# jumper_bed2.net
KiCad netlist of a schematic drawn in EAGLE
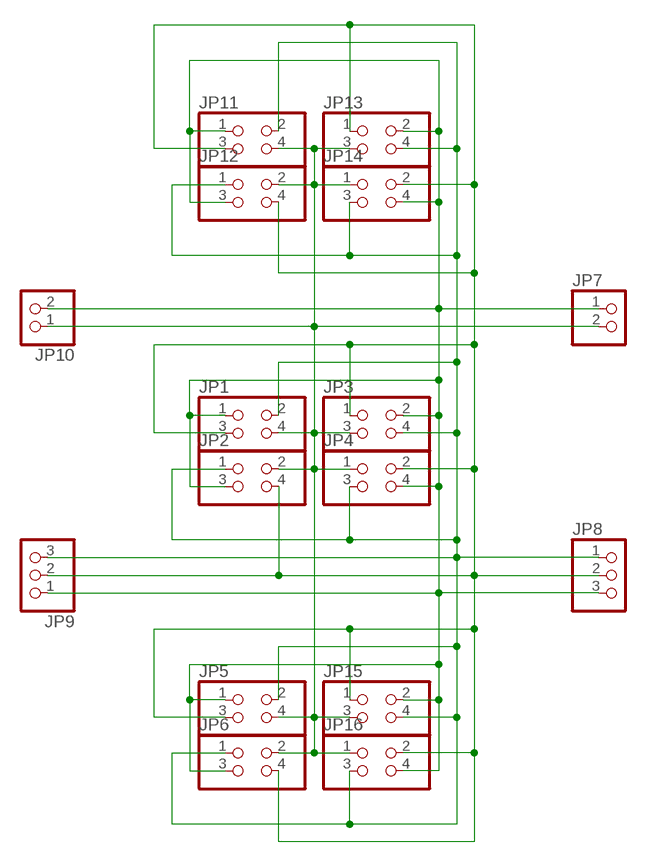
[diagram p0: schematic, sheet 1]

(export (version "E")
  (design (tool "Eeschema 10.0.6"))
  (components
    (comp (ref "JP1")
      (value "PINHD-2X2")
      (footprint "eagle-import:2X02")
      (libsource (lib "eagle-import") (part "PINHD-2X2"))
    )
    (comp (ref "JP2")
      (value "PINHD-2X2")
      (footprint "eagle-import:2X02")
      (libsource (lib "eagle-import") (part "PINHD-2X2"))
    )
    (comp (ref "JP3")
      (value "PINHD-2X2")
      (footprint "eagle-import:2X02")
      (libsource (lib "eagle-import") (part "PINHD-2X2"))
    )
    (comp (ref "JP4")
      (value "PINHD-2X2")
      (footprint "eagle-import:2X02")
      (libsource (lib "eagle-import") (part "PINHD-2X2"))
    )
    (comp (ref "JP5")
      (value "PINHD-2X2")
      (footprint "eagle-import:2X02")
      (libsource (lib "eagle-import") (part "PINHD-2X2"))
    )
    (comp (ref "JP6")
      (value "PINHD-2X2")
      (footprint "eagle-import:2X02")
      (libsource (lib "eagle-import") (part "PINHD-2X2"))
    )
    (comp (ref "JP7")
      (value "PINHD-1X2/90")
      (footprint "eagle-import:1X02_90")
      (libsource (lib "eagle-import") (part "PINHD-1X2/90"))
    )
    (comp (ref "JP8")
      (value "PINHD-1X3/90")
      (footprint "eagle-import:1X03_90")
      (libsource (lib "eagle-import") (part "PINHD-1X3/90"))
    )
    (comp (ref "JP9")
      (value "PINHD-1X31X03/90F")
      (footprint "eagle-import:1X03_90F")
      (libsource (lib "eagle-import") (part "PINHD-1X31X03/90F"))
    )
    (comp (ref "JP10")
      (value "PINHD-1X21X02/90F")
      (footprint "eagle-import:1X02_90F")
      (libsource (lib "eagle-import") (part "PINHD-1X21X02/90F"))
    )
    (comp (ref "JP11")
      (value "PINHD-2X2")
      (footprint "eagle-import:2X02")
      (libsource (lib "eagle-import") (part "PINHD-2X2"))
    )
    (comp (ref "JP12")
      (value "PINHD-2X2")
      (footprint "eagle-import:2X02")
      (libsource (lib "eagle-import") (part "PINHD-2X2"))
    )
    (comp (ref "JP13")
      (value "PINHD-2X2")
      (footprint "eagle-import:2X02")
      (libsource (lib "eagle-import") (part "PINHD-2X2"))
    )
    (comp (ref "JP14")
      (value "PINHD-2X2")
      (footprint "eagle-import:2X02")
      (libsource (lib "eagle-import") (part "PINHD-2X2"))
    )
    (comp (ref "JP15")
      (value "PINHD-2X2")
      (footprint "eagle-import:2X02")
      (libsource (lib "eagle-import") (part "PINHD-2X2"))
    )
    (comp (ref "JP16")
      (value "PINHD-2X2")
      (footprint "eagle-import:2X02")
      (libsource (lib "eagle-import") (part "PINHD-2X2"))
    )
  )
  (nets
    (net (code "1") (name "Net-(JP1-Pad1)") (class "Default")
      (node (ref "JP1") (pin "1") (pinfunction "1_1") (pintype "passive"))
      (node (ref "JP10") (pin "2") (pinfunction "2_2") (pintype "passive"))
      (node (ref "JP11") (pin "1") (pinfunction "1_1") (pintype "passive"))
      (node (ref "JP12") (pin "3") (pinfunction "3_3") (pintype "passive"))
      (node (ref "JP13") (pin "2") (pinfunction "2_2") (pintype "passive"))
      (node (ref "JP14") (pin "4") (pinfunction "4_4") (pintype "passive"))
      (node (ref "JP15") (pin "2") (pinfunction "2_2") (pintype "passive"))
      (node (ref "JP16") (pin "4") (pinfunction "4_4") (pintype "passive"))
      (node (ref "JP2") (pin "3") (pinfunction "3_3") (pintype "passive"))
      (node (ref "JP3") (pin "2") (pinfunction "2_2") (pintype "passive"))
      (node (ref "JP4") (pin "4") (pinfunction "4_4") (pintype "passive"))
      (node (ref "JP5") (pin "1") (pinfunction "1_1") (pintype "passive"))
      (node (ref "JP6") (pin "3") (pinfunction "3_3") (pintype "passive"))
      (node (ref "JP7") (pin "1") (pinfunction "1_1") (pintype "passive"))
      (node (ref "JP8") (pin "3") (pinfunction "3_3") (pintype "passive"))
      (node (ref "JP9") (pin "1") (pinfunction "1_1") (pintype "passive"))
    )
    (net (code "2") (name "Net-(JP1-Pad2)") (class "Default")
      (node (ref "JP1") (pin "2") (pinfunction "2_2") (pintype "passive"))
      (node (ref "JP11") (pin "2") (pinfunction "2_2") (pintype "passive"))
      (node (ref "JP12") (pin "1") (pinfunction "1_1") (pintype "passive"))
      (node (ref "JP13") (pin "4") (pinfunction "4_4") (pintype "passive"))
      (node (ref "JP14") (pin "3") (pinfunction "3_3") (pintype "passive"))
      (node (ref "JP15") (pin "4") (pinfunction "4_4") (pintype "passive"))
      (node (ref "JP16") (pin "3") (pinfunction "3_3") (pintype "passive"))
      (node (ref "JP2") (pin "1") (pinfunction "1_1") (pintype "passive"))
      (node (ref "JP3") (pin "4") (pinfunction "4_4") (pintype "passive"))
      (node (ref "JP4") (pin "3") (pinfunction "3_3") (pintype "passive"))
      (node (ref "JP5") (pin "2") (pinfunction "2_2") (pintype "passive"))
      (node (ref "JP6") (pin "1") (pinfunction "1_1") (pintype "passive"))
      (node (ref "JP8") (pin "1") (pinfunction "1_1") (pintype "passive"))
      (node (ref "JP9") (pin "3") (pinfunction "3_3") (pintype "passive"))
    )
    (net (code "3") (name "Net-(JP1-Pad3)") (class "Default")
      (node (ref "JP1") (pin "3") (pinfunction "3_3") (pintype "passive"))
      (node (ref "JP11") (pin "3") (pinfunction "3_3") (pintype "passive"))
      (node (ref "JP12") (pin "4") (pinfunction "4_4") (pintype "passive"))
      (node (ref "JP13") (pin "1") (pinfunction "1_1") (pintype "passive"))
      (node (ref "JP14") (pin "2") (pinfunction "2_2") (pintype "passive"))
      (node (ref "JP15") (pin "1") (pinfunction "1_1") (pintype "passive"))
      (node (ref "JP16") (pin "2") (pinfunction "2_2") (pintype "passive"))
      (node (ref "JP2") (pin "4") (pinfunction "4_4") (pintype "passive"))
      (node (ref "JP3") (pin "1") (pinfunction "1_1") (pintype "passive"))
      (node (ref "JP4") (pin "2") (pinfunction "2_2") (pintype "passive"))
      (node (ref "JP5") (pin "3") (pinfunction "3_3") (pintype "passive"))
      (node (ref "JP6") (pin "4") (pinfunction "4_4") (pintype "passive"))
      (node (ref "JP8") (pin "2") (pinfunction "2_2") (pintype "passive"))
      (node (ref "JP9") (pin "2") (pinfunction "2_2") (pintype "passive"))
    )
    (net (code "4") (name "Net-(JP1-Pad4)") (class "Default")
      (node (ref "JP1") (pin "4") (pinfunction "4_4") (pintype "passive"))
      (node (ref "JP10") (pin "1") (pinfunction "1_1") (pintype "passive"))
      (node (ref "JP11") (pin "4") (pinfunction "4_4") (pintype "passive"))
      (node (ref "JP12") (pin "2") (pinfunction "2_2") (pintype "passive"))
      (node (ref "JP13") (pin "3") (pinfunction "3_3") (pintype "passive"))
      (node (ref "JP14") (pin "1") (pinfunction "1_1") (pintype "passive"))
      (node (ref "JP15") (pin "3") (pinfunction "3_3") (pintype "passive"))
      (node (ref "JP16") (pin "1") (pinfunction "1_1") (pintype "passive"))
      (node (ref "JP2") (pin "2") (pinfunction "2_2") (pintype "passive"))
      (node (ref "JP3") (pin "3") (pinfunction "3_3") (pintype "passive"))
      (node (ref "JP4") (pin "1") (pinfunction "1_1") (pintype "passive"))
      (node (ref "JP5") (pin "4") (pinfunction "4_4") (pintype "passive"))
      (node (ref "JP6") (pin "2") (pinfunction "2_2") (pintype "passive"))
      (node (ref "JP7") (pin "2") (pinfunction "2_2") (pintype "passive"))
    )
  )
)
